# DCCGen_ATMEGA_V5.net
KiCad netlist of a schematic drawn in EAGLE
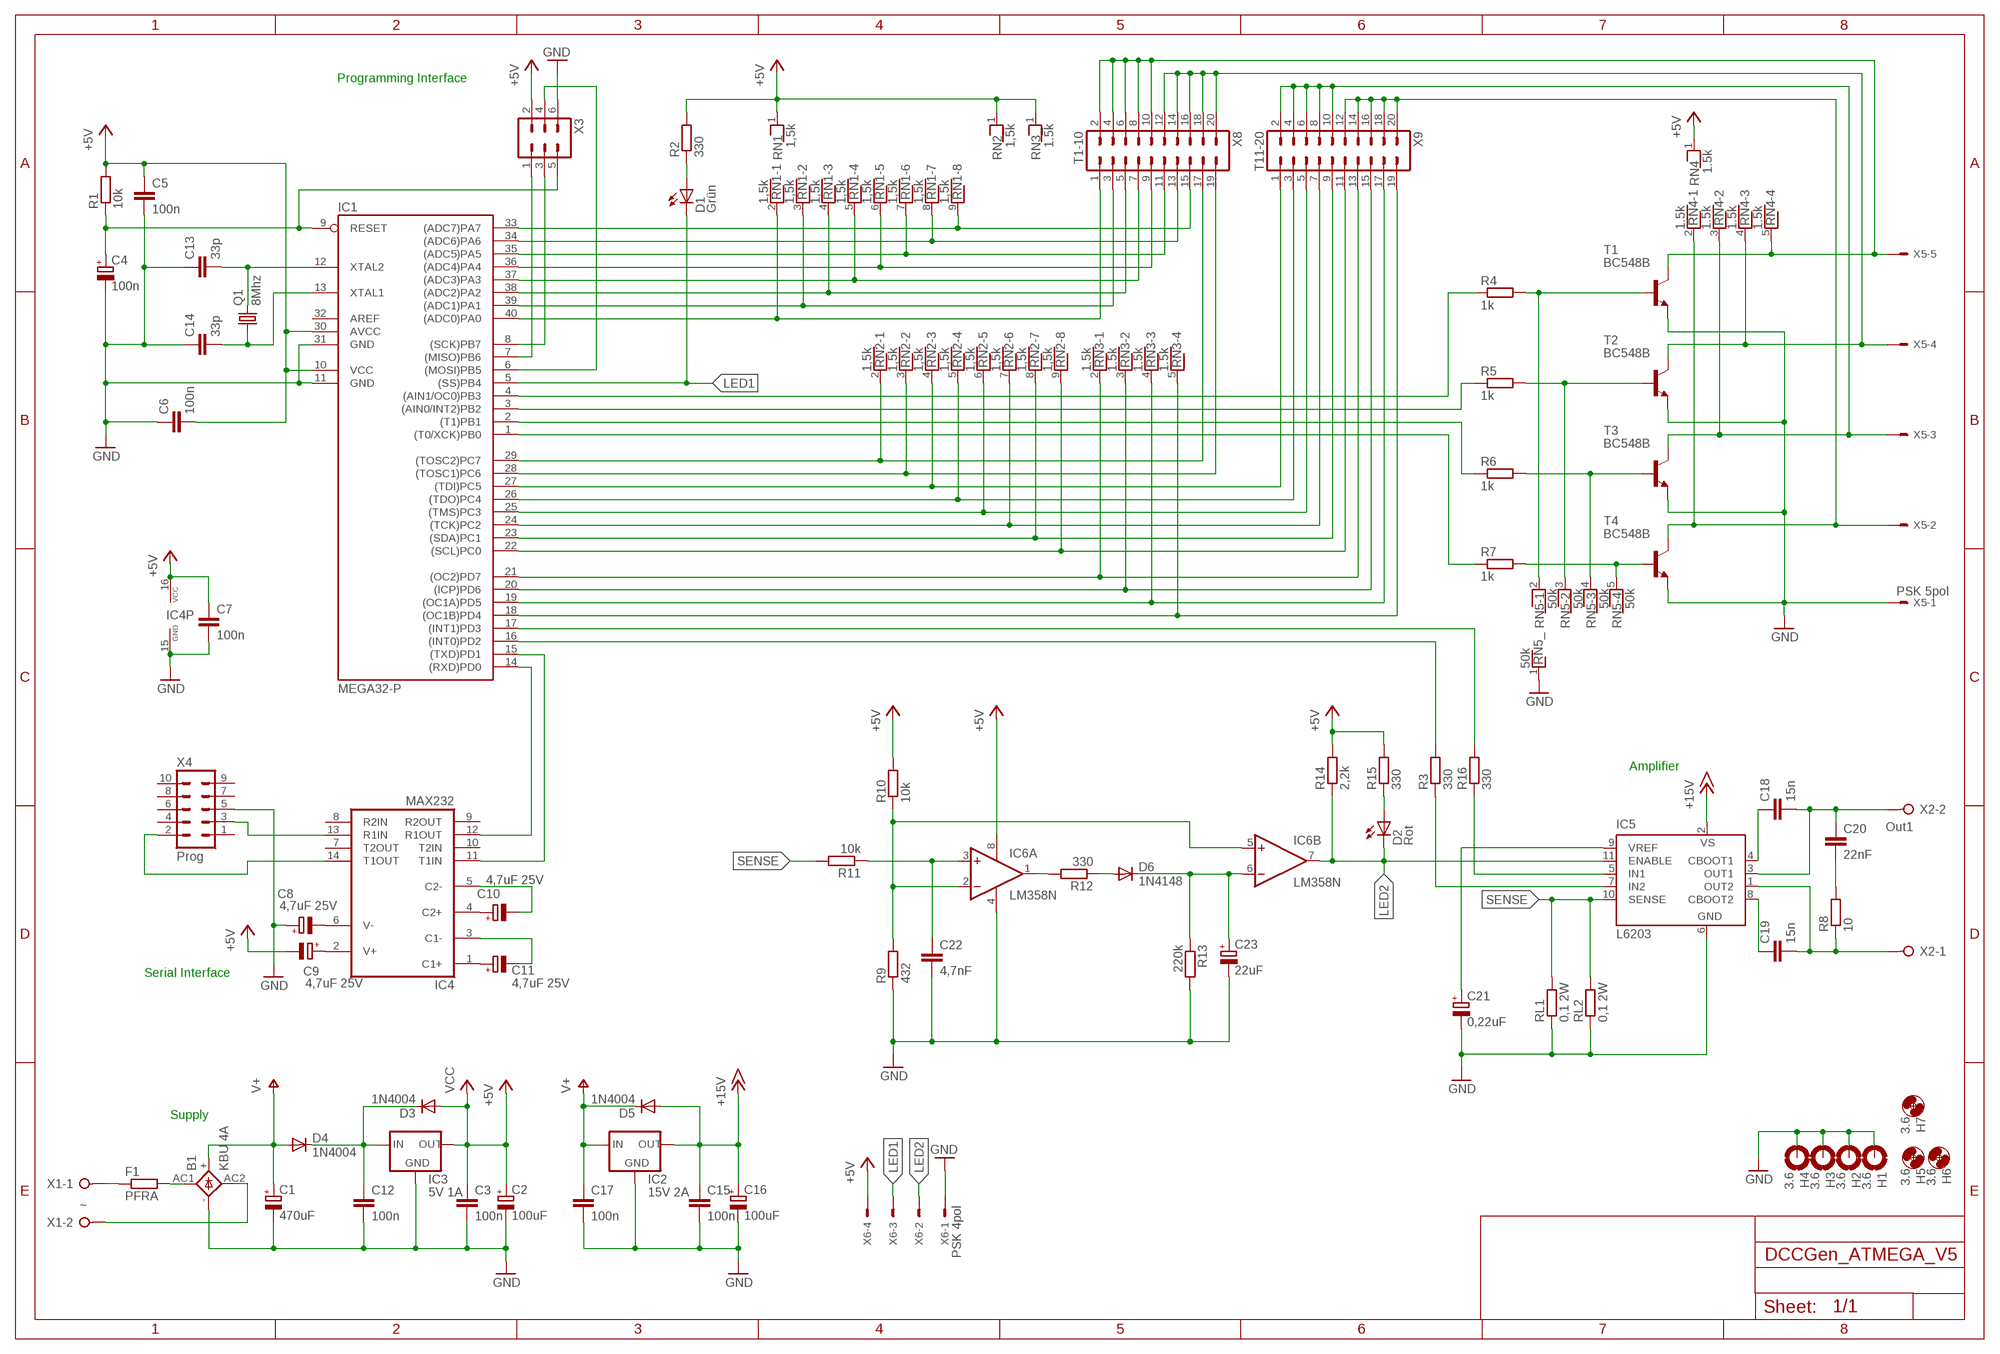
[diagram p0: schematic, sheet 1]

(export (version "E")
  (design (tool "Eeschema 10.0.6"))
  (components
    (comp (ref "B1")
      (value "KBU 4A")
      (footprint "eagle-import:KBU")
      (libsource (lib "eagle-import") (part "KBU"))
    )
    (comp (ref "C1")
      (value "470uF")
      (footprint "eagle-import:E5-13")
      (libsource (lib "eagle-import") (part "CPOL-EUE5-13"))
    )
    (comp (ref "C2")
      (value "100uF")
      (footprint "eagle-import:E2,5-7")
      (libsource (lib "eagle-import") (part "CPOL-EUE2.5-7"))
    )
    (comp (ref "C3")
      (value "100n")
      (footprint "eagle-import:C025-025X050")
      (libsource (lib "eagle-import") (part "C-EU025-025X050"))
    )
    (comp (ref "C4")
      (value "100n")
      (footprint "eagle-import:E2,5-5")
      (libsource (lib "eagle-import") (part "CPOL-EUE2.5-5"))
    )
    (comp (ref "C5")
      (value "100n")
      (footprint "eagle-import:C025-025X050")
      (libsource (lib "eagle-import") (part "C-EU025-025X050"))
    )
    (comp (ref "C6")
      (value "100n")
      (footprint "eagle-import:C025-025X050")
      (libsource (lib "eagle-import") (part "C-EU025-025X050"))
    )
    (comp (ref "C7")
      (value "100n")
      (footprint "eagle-import:C025-025X050")
      (libsource (lib "eagle-import") (part "C-EU025-025X050"))
    )
    (comp (ref "C8")
      (value "4,7uF 25V")
      (footprint "eagle-import:E2,5-6E")
      (libsource (lib "eagle-import") (part "CPOL-EUE2,5-6E"))
    )
    (comp (ref "C9")
      (value "4,7uF 25V")
      (footprint "eagle-import:E2,5-6E")
      (libsource (lib "eagle-import") (part "CPOL-EUE2,5-6E"))
    )
    (comp (ref "C10")
      (value "4,7uF 25V")
      (footprint "eagle-import:E2,5-6E")
      (libsource (lib "eagle-import") (part "CPOL-EUE2,5-6E"))
    )
    (comp (ref "C11")
      (value "4,7uF 25V")
      (footprint "eagle-import:E2,5-6E")
      (libsource (lib "eagle-import") (part "CPOL-EUE2,5-6E"))
    )
    (comp (ref "C12")
      (value "100n")
      (footprint "eagle-import:C025-025X050")
      (libsource (lib "eagle-import") (part "C-EU025-025X050"))
    )
    (comp (ref "C13")
      (value "33p")
      (footprint "eagle-import:C025-025X050")
      (libsource (lib "eagle-import") (part "C-EU025-025X050"))
    )
    (comp (ref "C14")
      (value "33p")
      (footprint "eagle-import:C025-025X050")
      (libsource (lib "eagle-import") (part "C-EU025-025X050"))
    )
    (comp (ref "C15")
      (value "100n")
      (footprint "eagle-import:C025-025X050")
      (libsource (lib "eagle-import") (part "C-EU025-025X050"))
    )
    (comp (ref "C16")
      (value "100uF")
      (footprint "eagle-import:E2,5-7")
      (libsource (lib "eagle-import") (part "CPOL-EUE2.5-7"))
    )
    (comp (ref "C17")
      (value "100n")
      (footprint "eagle-import:C025-025X050")
      (libsource (lib "eagle-import") (part "C-EU025-025X050"))
    )
    (comp (ref "C18")
      (value "15n")
      (footprint "eagle-import:C025-025X050")
      (libsource (lib "eagle-import") (part "C-EU025-025X050"))
    )
    (comp (ref "C19")
      (value "15n")
      (footprint "eagle-import:C025-025X050")
      (libsource (lib "eagle-import") (part "C-EU025-025X050"))
    )
    (comp (ref "C20")
      (value "22nF")
      (footprint "eagle-import:C025-025X050")
      (libsource (lib "eagle-import") (part "C-EU025-025X050"))
    )
    (comp (ref "C21")
      (value "0,22uF")
      (footprint "eagle-import:E2-5")
      (libsource (lib "eagle-import") (part "CPOL-EUE2-5"))
    )
    (comp (ref "C22")
      (value "4,7nF")
      (footprint "eagle-import:C025-025X050")
      (libsource (lib "eagle-import") (part "C-EU025-025X050"))
    )
    (comp (ref "C23")
      (value "22uF")
      (footprint "eagle-import:E2-5")
      (libsource (lib "eagle-import") (part "CPOL-EUE2-5"))
    )
    (comp (ref "D1")
      (value "Grün")
      (footprint "eagle-import:LED3MM")
      (libsource (lib "eagle-import") (part "LED3MM"))
    )
    (comp (ref "D2")
      (value "Rot")
      (footprint "eagle-import:LED3MM")
      (libsource (lib "eagle-import") (part "LED3MM"))
    )
    (comp (ref "D3")
      (value "1N4004")
      (footprint "eagle-import:DO41-10")
      (libsource (lib "eagle-import") (part "1N4004"))
    )
    (comp (ref "D4")
      (value "1N4004")
      (footprint "eagle-import:DO41-10")
      (libsource (lib "eagle-import") (part "1N4004"))
    )
    (comp (ref "D5")
      (value "1N4004")
      (footprint "eagle-import:DO41-10")
      (libsource (lib "eagle-import") (part "1N4004"))
    )
    (comp (ref "D6")
      (value "1N4148")
      (footprint "eagle-import:DO35-10")
      (libsource (lib "eagle-import") (part "1N4148DO35-10"))
    )
    (comp (ref "F1")
      (value "PFRA")
      (footprint "eagle-import:0204_5")
      (libsource (lib "eagle-import") (part "R-EU_0204/5"))
    )
    (comp (ref "H1")
      (value "3.6")
      (footprint "eagle-import:3,6-PAD")
      (libsource (lib "eagle-import") (part "MOUNT-PAD-ROUND3.6"))
    )
    (comp (ref "H2")
      (value "3.6")
      (footprint "eagle-import:3,6-PAD")
      (libsource (lib "eagle-import") (part "MOUNT-PAD-ROUND3.6"))
    )
    (comp (ref "H3")
      (value "3.6")
      (footprint "eagle-import:3,6-PAD")
      (libsource (lib "eagle-import") (part "MOUNT-PAD-ROUND3.6"))
    )
    (comp (ref "H4")
      (value "3.6")
      (footprint "eagle-import:3,6-PAD")
      (libsource (lib "eagle-import") (part "MOUNT-PAD-ROUND3.6"))
    )
    (comp (ref "H5")
      (value "3.6")
      (footprint "eagle-import:3,6")
      (libsource (lib "eagle-import") (part "MOUNT-HOLE3.6"))
    )
    (comp (ref "H6")
      (value "3.6")
      (footprint "eagle-import:3,6")
      (libsource (lib "eagle-import") (part "MOUNT-HOLE3.6"))
    )
    (comp (ref "H7")
      (value "3.6")
      (footprint "eagle-import:3,6")
      (libsource (lib "eagle-import") (part "MOUNT-HOLE3.6"))
    )
    (comp (ref "IC1")
      (value "MEGA32-P")
      (footprint "eagle-import:DIL40")
      (fields (field (name "MPN") "ATMEGA32-16PU"))
      (libsource (lib "eagle-import") (part "MEGA32-P"))
    )
    (comp (ref "IC2")
      (value "15V 2A")
      (footprint "eagle-import:78XXS")
      (libsource (lib "eagle-import") (part "78XXS"))
    )
    (comp (ref "IC3")
      (value "5V 1A")
      (footprint "eagle-import:78XXS")
      (libsource (lib "eagle-import") (part "78XXS"))
    )
    (comp (ref "IC4")
      (value "MAX232")
      (footprint "eagle-import:DIL16")
      (libsource (lib "eagle-import") (part "MAX232"))
    )
    (comp (ref "IC5")
      (value "L6203")
      (footprint "eagle-import:MULTIWATT-11")
      (libsource (lib "eagle-import") (part "L6203"))
    )
    (comp (ref "IC6")
      (value "LM358N")
      (footprint "eagle-import:DIL08")
      (libsource (lib "eagle-import") (part "LM358N"))
    )
    (comp (ref "Q1")
      (value "8Mhz")
      (footprint "eagle-import:HC49U-V")
      (libsource (lib "eagle-import") (part "CRYSTALHC49U-V"))
    )
    (comp (ref "R1")
      (value "10k")
      (footprint "eagle-import:0207_10")
      (libsource (lib "eagle-import") (part "R-EU_0207/10"))
    )
    (comp (ref "R2")
      (value "330")
      (footprint "eagle-import:0207_10")
      (libsource (lib "eagle-import") (part "R-EU_0207/10"))
    )
    (comp (ref "R3")
      (value "330")
      (footprint "eagle-import:0207_10")
      (libsource (lib "eagle-import") (part "R-EU_0207/10"))
    )
    (comp (ref "R4")
      (value "1k")
      (footprint "eagle-import:0207_10")
      (libsource (lib "eagle-import") (part "R-EU_0207/10"))
    )
    (comp (ref "R5")
      (value "1k")
      (footprint "eagle-import:0207_10")
      (libsource (lib "eagle-import") (part "R-EU_0207/10"))
    )
    (comp (ref "R6")
      (value "1k")
      (footprint "eagle-import:0207_10")
      (libsource (lib "eagle-import") (part "R-EU_0207/10"))
    )
    (comp (ref "R7")
      (value "1k")
      (footprint "eagle-import:0207_10")
      (libsource (lib "eagle-import") (part "R-EU_0207/10"))
    )
    (comp (ref "R8")
      (value "10")
      (footprint "eagle-import:0207_10")
      (libsource (lib "eagle-import") (part "R-EU_0207/10"))
    )
    (comp (ref "R9")
      (value "432")
      (footprint "eagle-import:0207_10")
      (libsource (lib "eagle-import") (part "R-EU_0207/10"))
    )
    (comp (ref "R10")
      (value "10k")
      (footprint "eagle-import:0207_10")
      (libsource (lib "eagle-import") (part "R-EU_0207/10"))
    )
    (comp (ref "R11")
      (value "10k")
      (footprint "eagle-import:0207_10")
      (libsource (lib "eagle-import") (part "R-EU_0207/10"))
    )
    (comp (ref "R12")
      (value "330")
      (footprint "eagle-import:0207_10")
      (libsource (lib "eagle-import") (part "R-EU_0207/10"))
    )
    (comp (ref "R13")
      (value "220k")
      (footprint "eagle-import:0207_10")
      (libsource (lib "eagle-import") (part "R-EU_0207/10"))
    )
    (comp (ref "R14")
      (value "2,2k")
      (footprint "eagle-import:0207_10")
      (libsource (lib "eagle-import") (part "R-EU_0207/10"))
    )
    (comp (ref "R15")
      (value "330")
      (footprint "eagle-import:0207_10")
      (libsource (lib "eagle-import") (part "R-EU_0207/10"))
    )
    (comp (ref "R16")
      (value "330")
      (footprint "eagle-import:0207_10")
      (libsource (lib "eagle-import") (part "R-EU_0207/10"))
    )
    (comp (ref "RL1")
      (value "0,1 2W")
      (footprint "eagle-import:0617_17")
      (libsource (lib "eagle-import") (part "R-EU_0617/17"))
    )
    (comp (ref "RL2")
      (value "0,1 2W")
      (footprint "eagle-import:0617_17")
      (libsource (lib "eagle-import") (part "R-EU_0617/17"))
    )
    (comp (ref "RN1")
      (value "1,5k")
      (footprint "eagle-import:RN-9")
      (libsource (lib "eagle-import") (part "RNX8"))
    )
    (comp (ref "RN2")
      (value "1,5k")
      (footprint "eagle-import:RN-9")
      (libsource (lib "eagle-import") (part "RNX8"))
    )
    (comp (ref "RN3")
      (value "1.5k")
      (footprint "eagle-import:RN-5")
      (fields (field (name "OC_FARNELL") "unknown") (field (name "OC_NEWARK") "unknown"))
      (libsource (lib "eagle-import") (part "RNX4"))
    )
    (comp (ref "RN4")
      (value "1.5k")
      (footprint "eagle-import:RN-5")
      (libsource (lib "eagle-import") (part "RNX4"))
    )
    (comp (ref "RN5")
      (value "50k")
      (footprint "eagle-import:RN-5")
      (libsource (lib "eagle-import") (part "RNX4"))
    )
    (comp (ref "T1")
      (value "BC548B")
      (footprint "eagle-import:TO92-EBC")
      (libsource (lib "eagle-import") (part "BC548B"))
    )
    (comp (ref "T2")
      (value "BC548B")
      (footprint "eagle-import:TO92-EBC")
      (libsource (lib "eagle-import") (part "BC548B"))
    )
    (comp (ref "T3")
      (value "BC548B")
      (footprint "eagle-import:TO92-EBC")
      (libsource (lib "eagle-import") (part "BC548B"))
    )
    (comp (ref "T4")
      (value "BC548B")
      (footprint "eagle-import:TO92-EBC")
      (libsource (lib "eagle-import") (part "BC548B"))
    )
    (comp (ref "X1")
      (value "~")
      (footprint "eagle-import:W237-132")
      (libsource (lib "eagle-import") (part "W237-02P"))
    )
    (comp (ref "X2")
      (value "Out1")
      (footprint "eagle-import:W237-132")
      (libsource (lib "eagle-import") (part "W237-02P"))
    )
    (comp (ref "X3")
      (value "ML6")
      (footprint "eagle-import:ML6")
      (libsource (lib "eagle-import") (part "ML6"))
    )
    (comp (ref "X4")
      (value "Prog")
      (footprint "eagle-import:ML10")
      (libsource (lib "eagle-import") (part "ML10"))
    )
    (comp (ref "X5")
      (value "PSK 5pol")
      (footprint "eagle-import:6410-05")
      (libsource (lib "eagle-import") (part "22-?-0527-2051"))
    )
    (comp (ref "X6")
      (value "PSK 4pol")
      (footprint "eagle-import:6410-04")
      (libsource (lib "eagle-import") (part "22-?-0427-2041"))
    )
    (comp (ref "X8")
      (value "T1-10")
      (footprint "eagle-import:ML20")
      (libsource (lib "eagle-import") (part "ML20"))
    )
    (comp (ref "X9")
      (value "T11-20")
      (footprint "eagle-import:ML20")
      (libsource (lib "eagle-import") (part "ML20"))
    )
  )
  (nets
    (net (code "1") (name "+5V") (class "Default")
      (node (ref "C2") (pin "+") (pinfunction "+_+") (pintype "passive"))
      (node (ref "C3") (pin "1") (pinfunction "1_1") (pintype "passive"))
      (node (ref "C5") (pin "1") (pinfunction "1_1") (pintype "passive"))
      (node (ref "C6") (pin "2") (pinfunction "2_2") (pintype "passive"))
      (node (ref "C7") (pin "1") (pinfunction "1_1") (pintype "passive"))
      (node (ref "C9") (pin "-") (pinfunction "-_-") (pintype "passive"))
      (node (ref "D3") (pin "A") (pinfunction "A_A") (pintype "passive"))
      (node (ref "IC1") (pin "10") (pinfunction "VCC_10") (pintype "power_in"))
      (node (ref "IC1") (pin "30") (pinfunction "AVCC_30") (pintype "power_in"))
      (node (ref "IC3") (pin "OUT") (pinfunction "OUT_OUT") (pintype "passive"))
      (node (ref "IC4") (pin "16") (pinfunction "VCC_16") (pintype "power_in"))
      (node (ref "IC6") (pin "8") (pinfunction "V+_8") (pintype "power_in"))
      (node (ref "R1") (pin "2") (pinfunction "2_2") (pintype "passive"))
      (node (ref "R10") (pin "2") (pinfunction "2_2") (pintype "passive"))
      (node (ref "R14") (pin "2") (pinfunction "2_2") (pintype "passive"))
      (node (ref "R15") (pin "2") (pinfunction "2_2") (pintype "passive"))
      (node (ref "R2") (pin "2") (pinfunction "2_2") (pintype "passive"))
      (node (ref "RN1") (pin "1") (pinfunction "1_1") (pintype "passive"))
      (node (ref "RN2") (pin "1") (pinfunction "1_1") (pintype "passive"))
      (node (ref "RN3") (pin "1") (pinfunction "1_1") (pintype "passive"))
      (node (ref "RN4") (pin "1") (pinfunction "1_1") (pintype "passive"))
      (node (ref "X3") (pin "2") (pinfunction "2_2") (pintype "passive"))
      (node (ref "X6") (pin "4") (pinfunction "S_4") (pintype "passive"))
    )
    (net (code "2") (name "+15V") (class "Default")
      (node (ref "C15") (pin "1") (pinfunction "1_1") (pintype "passive"))
      (node (ref "C16") (pin "+") (pinfunction "+_+") (pintype "passive"))
      (node (ref "D5") (pin "A") (pinfunction "A_A") (pintype "passive"))
      (node (ref "IC2") (pin "OUT") (pinfunction "OUT_OUT") (pintype "passive"))
      (node (ref "IC5") (pin "2") (pinfunction "VS_2") (pintype "power_in"))
    )
    (net (code "3") (name "GND") (class "Default")
      (node (ref "B1") (pin "-") (pinfunction "-_-") (pintype "passive"))
      (node (ref "C1") (pin "-") (pinfunction "-_-") (pintype "passive"))
      (node (ref "C12") (pin "2") (pinfunction "2_2") (pintype "passive"))
      (node (ref "C13") (pin "1") (pinfunction "1_1") (pintype "passive"))
      (node (ref "C14") (pin "1") (pinfunction "1_1") (pintype "passive"))
      (node (ref "C15") (pin "2") (pinfunction "2_2") (pintype "passive"))
      (node (ref "C16") (pin "-") (pinfunction "-_-") (pintype "passive"))
      (node (ref "C17") (pin "2") (pinfunction "2_2") (pintype "passive"))
      (node (ref "C2") (pin "-") (pinfunction "-_-") (pintype "passive"))
      (node (ref "C21") (pin "-") (pinfunction "-_-") (pintype "passive"))
      (node (ref "C22") (pin "2") (pinfunction "2_2") (pintype "passive"))
      (node (ref "C23") (pin "-") (pinfunction "-_-") (pintype "passive"))
      (node (ref "C3") (pin "2") (pinfunction "2_2") (pintype "passive"))
      (node (ref "C4") (pin "-") (pinfunction "-_-") (pintype "passive"))
      (node (ref "C5") (pin "2") (pinfunction "2_2") (pintype "passive"))
      (node (ref "C6") (pin "1") (pinfunction "1_1") (pintype "passive"))
      (node (ref "C7") (pin "2") (pinfunction "2_2") (pintype "passive"))
      (node (ref "C8") (pin "+") (pinfunction "+_+") (pintype "passive"))
      (node (ref "H1") (pin "B3,6") (pinfunction "MOUNT_B3,6") (pintype "passive"))
      (node (ref "H2") (pin "B3,6") (pinfunction "MOUNT_B3,6") (pintype "passive"))
      (node (ref "H3") (pin "B3,6") (pinfunction "MOUNT_B3,6") (pintype "passive"))
      (node (ref "H4") (pin "B3,6") (pinfunction "MOUNT_B3,6") (pintype "passive"))
      (node (ref "IC1") (pin "11") (pinfunction "GND_11") (pintype "power_in"))
      (node (ref "IC1") (pin "31") (pinfunction "GND_31") (pintype "power_in"))
      (node (ref "IC2") (pin "GND") (pinfunction "GND_GND") (pintype "input"))
      (node (ref "IC3") (pin "GND") (pinfunction "GND_GND") (pintype "input"))
      (node (ref "IC4") (pin "15") (pinfunction "GND_15") (pintype "power_in"))
      (node (ref "IC5") (pin "6") (pinfunction "GND_6") (pintype "power_in"))
      (node (ref "IC6") (pin "4") (pinfunction "V-_4") (pintype "power_in"))
      (node (ref "R13") (pin "2") (pinfunction "2_2") (pintype "passive"))
      (node (ref "R9") (pin "1") (pinfunction "1_1") (pintype "passive"))
      (node (ref "RL1") (pin "1") (pinfunction "1_1") (pintype "passive"))
      (node (ref "RL2") (pin "1") (pinfunction "1_1") (pintype "passive"))
      (node (ref "RN5") (pin "1") (pinfunction "1_1") (pintype "passive"))
      (node (ref "T1") (pin "E") (pinfunction "E_E") (pintype "passive"))
      (node (ref "T2") (pin "E") (pinfunction "E_E") (pintype "passive"))
      (node (ref "T3") (pin "E") (pinfunction "E_E") (pintype "passive"))
      (node (ref "T4") (pin "E") (pinfunction "E_E") (pintype "passive"))
      (node (ref "X3") (pin "6") (pinfunction "6_6") (pintype "passive"))
      (node (ref "X4") (pin "5") (pinfunction "5_5") (pintype "passive"))
      (node (ref "X5") (pin "1") (pinfunction "S_1") (pintype "passive"))
      (node (ref "X6") (pin "1") (pinfunction "S_1") (pintype "passive"))
    )
    (net (code "4") (name "LED1") (class "Default")
      (node (ref "D1") (pin "K") (pinfunction "C_K") (pintype "passive"))
      (node (ref "IC1") (pin "5") (pinfunction "(SS)PB4_5") (pintype "bidirectional"))
      (node (ref "X6") (pin "3") (pinfunction "S_3") (pintype "passive"))
    )
    (net (code "5") (name "LED2") (class "Default")
      (node (ref "D2") (pin "K") (pinfunction "C_K") (pintype "passive"))
      (node (ref "IC5") (pin "11") (pinfunction "ENABLE_11") (pintype "input"))
      (node (ref "IC6") (pin "7") (pinfunction "OUT_7") (pintype "output"))
      (node (ref "R14") (pin "1") (pinfunction "1_1") (pintype "passive"))
      (node (ref "X6") (pin "2") (pinfunction "S_2") (pintype "passive"))
    )
    (net (code "6") (name "Net-(B1-PadAC1)") (class "Default")
      (node (ref "B1") (pin "AC1") (pinfunction "AC1_AC1") (pintype "passive"))
      (node (ref "F1") (pin "2") (pinfunction "2_2") (pintype "passive"))
    )
    (net (code "7") (name "Net-(C12-Pad1)") (class "Default")
      (node (ref "C12") (pin "1") (pinfunction "1_1") (pintype "passive"))
      (node (ref "D3") (pin "C") (pinfunction "C_C") (pintype "passive"))
      (node (ref "D4") (pin "C") (pinfunction "C_C") (pintype "passive"))
      (node (ref "IC3") (pin "IN") (pinfunction "IN_IN") (pintype "input"))
    )
    (net (code "8") (name "Net-(C20-Pad2)") (class "Default")
      (node (ref "C20") (pin "2") (pinfunction "2_2") (pintype "passive"))
      (node (ref "R8") (pin "2") (pinfunction "2_2") (pintype "passive"))
    )
    (net (code "9") (name "Net-(D1-PadA)") (class "Default")
      (node (ref "D1") (pin "A") (pinfunction "A_A") (pintype "passive"))
      (node (ref "R2") (pin "1") (pinfunction "1_1") (pintype "passive"))
    )
    (net (code "10") (name "Net-(D2-PadA)") (class "Default")
      (node (ref "D2") (pin "A") (pinfunction "A_A") (pintype "passive"))
      (node (ref "R15") (pin "1") (pinfunction "1_1") (pintype "passive"))
    )
    (net (code "11") (name "Net-(D6-PadA)") (class "Default")
      (node (ref "D6") (pin "A") (pinfunction "A_A") (pintype "passive"))
      (node (ref "R12") (pin "1") (pinfunction "1_1") (pintype "passive"))
    )
    (net (code "12") (name "Net-(IC1-(ADC0)PA0)") (class "Default")
      (node (ref "IC1") (pin "40") (pinfunction "(ADC0)PA0_40") (pintype "bidirectional"))
      (node (ref "RN1") (pin "2") (pinfunction "1_2") (pintype "passive"))
      (node (ref "X8") (pin "1") (pinfunction "1_1") (pintype "passive"))
    )
    (net (code "13") (name "Net-(IC1-(ADC1)PA1)") (class "Default")
      (node (ref "IC1") (pin "39") (pinfunction "(ADC1)PA1_39") (pintype "bidirectional"))
      (node (ref "RN1") (pin "3") (pinfunction "1_3") (pintype "passive"))
      (node (ref "X8") (pin "3") (pinfunction "3_3") (pintype "passive"))
    )
    (net (code "14") (name "Net-(IC1-(ADC2)PA2)") (class "Default")
      (node (ref "IC1") (pin "38") (pinfunction "(ADC2)PA2_38") (pintype "bidirectional"))
      (node (ref "RN1") (pin "4") (pinfunction "1_4") (pintype "passive"))
      (node (ref "X8") (pin "5") (pinfunction "5_5") (pintype "passive"))
    )
    (net (code "15") (name "Net-(IC1-(ADC3)PA3)") (class "Default")
      (node (ref "IC1") (pin "37") (pinfunction "(ADC3)PA3_37") (pintype "bidirectional"))
      (node (ref "RN1") (pin "5") (pinfunction "1_5") (pintype "passive"))
      (node (ref "X8") (pin "7") (pinfunction "7_7") (pintype "passive"))
    )
    (net (code "16") (name "Net-(IC1-(ADC4)PA4)") (class "Default")
      (node (ref "IC1") (pin "36") (pinfunction "(ADC4)PA4_36") (pintype "bidirectional"))
      (node (ref "RN1") (pin "6") (pinfunction "1_6") (pintype "passive"))
      (node (ref "X8") (pin "9") (pinfunction "9_9") (pintype "passive"))
    )
    (net (code "17") (name "Net-(IC1-(ADC5)PA5)") (class "Default")
      (node (ref "IC1") (pin "35") (pinfunction "(ADC5)PA5_35") (pintype "bidirectional"))
      (node (ref "RN1") (pin "7") (pinfunction "1_7") (pintype "passive"))
      (node (ref "X8") (pin "11") (pinfunction "11_11") (pintype "passive"))
    )
    (net (code "18") (name "Net-(IC1-(ADC6)PA6)") (class "Default")
      (node (ref "IC1") (pin "34") (pinfunction "(ADC6)PA6_34") (pintype "bidirectional"))
      (node (ref "RN1") (pin "8") (pinfunction "1_8") (pintype "passive"))
      (node (ref "X8") (pin "13") (pinfunction "13_13") (pintype "passive"))
    )
    (net (code "19") (name "Net-(IC1-(ADC7)PA7)") (class "Default")
      (node (ref "IC1") (pin "33") (pinfunction "(ADC7)PA7_33") (pintype "bidirectional"))
      (node (ref "RN1") (pin "9") (pinfunction "1_9") (pintype "passive"))
      (node (ref "X8") (pin "15") (pinfunction "15_15") (pintype "passive"))
    )
    (net (code "20") (name "Net-(IC1-(AIN0{slash}INT2)PB2)") (class "Default")
      (node (ref "IC1") (pin "3") (pinfunction "(AIN0/INT2)PB2_3") (pintype "bidirectional"))
      (node (ref "R5") (pin "1") (pinfunction "1_1") (pintype "passive"))
    )
    (net (code "21") (name "Net-(IC1-(AIN1{slash}OC0)PB3)") (class "Default")
      (node (ref "IC1") (pin "4") (pinfunction "(AIN1/OC0)PB3_4") (pintype "bidirectional"))
      (node (ref "R4") (pin "1") (pinfunction "1_1") (pintype "passive"))
    )
    (net (code "22") (name "Net-(IC1-(ICP)PD6)") (class "Default")
      (node (ref "IC1") (pin "20") (pinfunction "(ICP)PD6_20") (pintype "bidirectional"))
      (node (ref "RN3") (pin "3") (pinfunction "1_3") (pintype "passive"))
      (node (ref "X9") (pin "15") (pinfunction "15_15") (pintype "passive"))
    )
    (net (code "23") (name "Net-(IC1-(INT0)PD2)") (class "Default")
      (node (ref "IC1") (pin "16") (pinfunction "(INT0)PD2_16") (pintype "bidirectional"))
      (node (ref "R3") (pin "2") (pinfunction "2_2") (pintype "passive"))
    )
    (net (code "24") (name "Net-(IC1-(INT1)PD3)") (class "Default")
      (node (ref "IC1") (pin "17") (pinfunction "(INT1)PD3_17") (pintype "bidirectional"))
      (node (ref "R16") (pin "2") (pinfunction "2_2") (pintype "passive"))
    )
    (net (code "25") (name "Net-(IC1-(MISO)PB6)") (class "Default")
      (node (ref "IC1") (pin "7") (pinfunction "(MISO)PB6_7") (pintype "bidirectional"))
      (node (ref "X3") (pin "1") (pinfunction "1_1") (pintype "passive"))
    )
    (net (code "26") (name "Net-(IC1-(MOSI)PB5)") (class "Default")
      (node (ref "IC1") (pin "6") (pinfunction "(MOSI)PB5_6") (pintype "bidirectional"))
      (node (ref "X3") (pin "4") (pinfunction "4_4") (pintype "passive"))
    )
    (net (code "27") (name "Net-(IC1-(OC1A)PD5)") (class "Default")
      (node (ref "IC1") (pin "19") (pinfunction "(OC1A)PD5_19") (pintype "bidirectional"))
      (node (ref "RN3") (pin "4") (pinfunction "1_4") (pintype "passive"))
      (node (ref "X9") (pin "17") (pinfunction "17_17") (pintype "passive"))
    )
    (net (code "28") (name "Net-(IC1-(OC1B)PD4)") (class "Default")
      (node (ref "IC1") (pin "18") (pinfunction "(OC1B)PD4_18") (pintype "bidirectional"))
      (node (ref "RN3") (pin "5") (pinfunction "1_5") (pintype "passive"))
      (node (ref "X9") (pin "19") (pinfunction "19_19") (pintype "passive"))
    )
    (net (code "29") (name "Net-(IC1-(OC2)PD7)") (class "Default")
      (node (ref "IC1") (pin "21") (pinfunction "(OC2)PD7_21") (pintype "bidirectional"))
      (node (ref "RN3") (pin "2") (pinfunction "1_2") (pintype "passive"))
      (node (ref "X9") (pin "13") (pinfunction "13_13") (pintype "passive"))
    )
    (net (code "30") (name "Net-(IC1-(RXD)PD0)") (class "Default")
      (node (ref "IC1") (pin "14") (pinfunction "(RXD)PD0_14") (pintype "bidirectional"))
      (node (ref "IC4") (pin "12") (pinfunction "R1OUT_12") (pintype "output"))
    )
    (net (code "31") (name "Net-(IC1-(SCK)PB7)") (class "Default")
      (node (ref "IC1") (pin "8") (pinfunction "(SCK)PB7_8") (pintype "bidirectional"))
      (node (ref "X3") (pin "3") (pinfunction "3_3") (pintype "passive"))
    )
    (net (code "32") (name "Net-(IC1-(SCL)PC0)") (class "Default")
      (node (ref "IC1") (pin "22") (pinfunction "(SCL)PC0_22") (pintype "bidirectional"))
      (node (ref "RN2") (pin "9") (pinfunction "1_9") (pintype "passive"))
      (node (ref "X9") (pin "11") (pinfunction "11_11") (pintype "passive"))
    )
    (net (code "33") (name "Net-(IC1-(SDA)PC1)") (class "Default")
      (node (ref "IC1") (pin "23") (pinfunction "(SDA)PC1_23") (pintype "bidirectional"))
      (node (ref "RN2") (pin "8") (pinfunction "1_8") (pintype "passive"))
      (node (ref "X9") (pin "9") (pinfunction "9_9") (pintype "passive"))
    )
    (net (code "34") (name "Net-(IC1-(T0{slash}XCK)PB0)") (class "Default")
      (node (ref "IC1") (pin "1") (pinfunction "(T0/XCK)PB0_1") (pintype "bidirectional"))
      (node (ref "R7") (pin "1") (pinfunction "1_1") (pintype "passive"))
    )
    (net (code "35") (name "Net-(IC1-(T1)PB1)") (class "Default")
      (node (ref "IC1") (pin "2") (pinfunction "(T1)PB1_2") (pintype "bidirectional"))
      (node (ref "R6") (pin "1") (pinfunction "1_1") (pintype "passive"))
    )
    (net (code "36") (name "Net-(IC1-(TCK)PC2)") (class "Default")
      (node (ref "IC1") (pin "24") (pinfunction "(TCK)PC2_24") (pintype "bidirectional"))
      (node (ref "RN2") (pin "7") (pinfunction "1_7") (pintype "passive"))
      (node (ref "X9") (pin "7") (pinfunction "7_7") (pintype "passive"))
    )
    (net (code "37") (name "Net-(IC1-(TDI)PC5)") (class "Default")
      (node (ref "IC1") (pin "27") (pinfunction "(TDI)PC5_27") (pintype "bidirectional"))
      (node (ref "RN2") (pin "4") (pinfunction "1_4") (pintype "passive"))
      (node (ref "X9") (pin "1") (pinfunction "1_1") (pintype "passive"))
    )
    (net (code "38") (name "Net-(IC1-(TDO)PC4)") (class "Default")
      (node (ref "IC1") (pin "26") (pinfunction "(TDO)PC4_26") (pintype "bidirectional"))
      (node (ref "RN2") (pin "5") (pinfunction "1_5") (pintype "passive"))
      (node (ref "X9") (pin "3") (pinfunction "3_3") (pintype "passive"))
    )
    (net (code "39") (name "Net-(IC1-(TMS)PC3)") (class "Default")
      (node (ref "IC1") (pin "25") (pinfunction "(TMS)PC3_25") (pintype "bidirectional"))
      (node (ref "RN2") (pin "6") (pinfunction "1_6") (pintype "passive"))
      (node (ref "X9") (pin "5") (pinfunction "5_5") (pintype "passive"))
    )
    (net (code "40") (name "Net-(IC1-(TOSC1)PC6)") (class "Default")
      (node (ref "IC1") (pin "28") (pinfunction "(TOSC1)PC6_28") (pintype "bidirectional"))
      (node (ref "RN2") (pin "3") (pinfunction "1_3") (pintype "passive"))
      (node (ref "X8") (pin "19") (pinfunction "19_19") (pintype "passive"))
    )
    (net (code "41") (name "Net-(IC1-(TOSC2)PC7)") (class "Default")
      (node (ref "IC1") (pin "29") (pinfunction "(TOSC2)PC7_29") (pintype "bidirectional"))
      (node (ref "RN2") (pin "2") (pinfunction "1_2") (pintype "passive"))
      (node (ref "X8") (pin "17") (pinfunction "17_17") (pintype "passive"))
    )
    (net (code "42") (name "Net-(IC1-(TXD)PD1)") (class "Default")
      (node (ref "IC1") (pin "15") (pinfunction "(TXD)PD1_15") (pintype "bidirectional"))
      (node (ref "IC4") (pin "11") (pinfunction "T1IN_11") (pintype "input"))
    )
    (net (code "43") (name "Net-(IC1-RESET)") (class "Default")
      (node (ref "C4") (pin "+") (pinfunction "+_+") (pintype "passive"))
      (node (ref "IC1") (pin "9") (pinfunction "RESET_9") (pintype "input"))
      (node (ref "R1") (pin "1") (pinfunction "1_1") (pintype "passive"))
      (node (ref "X3") (pin "5") (pinfunction "5_5") (pintype "passive"))
    )
    (net (code "44") (name "Net-(IC1-XTAL1)") (class "Default")
      (node (ref "C14") (pin "2") (pinfunction "2_2") (pintype "passive"))
      (node (ref "IC1") (pin "13") (pinfunction "XTAL1_13") (pintype "bidirectional"))
      (node (ref "Q1") (pin "1") (pinfunction "1_1") (pintype "passive"))
    )
    (net (code "45") (name "Net-(IC1-XTAL2)") (class "Default")
      (node (ref "C13") (pin "2") (pinfunction "2_2") (pintype "passive"))
      (node (ref "IC1") (pin "12") (pinfunction "XTAL2_12") (pintype "bidirectional"))
      (node (ref "Q1") (pin "2") (pinfunction "2_2") (pintype "passive"))
    )
    (net (code "46") (name "Net-(IC4A-C1+)") (class "Default")
      (node (ref "C11") (pin "+") (pinfunction "+_+") (pintype "passive"))
      (node (ref "IC4") (pin "1") (pinfunction "C1+_1") (pintype "bidirectional"))
    )
    (net (code "47") (name "Net-(IC4A-C1-)") (class "Default")
      (node (ref "C11") (pin "-") (pinfunction "-_-") (pintype "passive"))
      (node (ref "IC4") (pin "3") (pinfunction "C1-_3") (pintype "bidirectional"))
    )
    (net (code "48") (name "Net-(IC4A-C2+)") (class "Default")
      (node (ref "C10") (pin "+") (pinfunction "+_+") (pintype "passive"))
      (node (ref "IC4") (pin "4") (pinfunction "C2+_4") (pintype "bidirectional"))
    )
    (net (code "49") (name "Net-(IC4A-C2-)") (class "Default")
      (node (ref "C10") (pin "-") (pinfunction "-_-") (pintype "passive"))
      (node (ref "IC4") (pin "5") (pinfunction "C2-_5") (pintype "bidirectional"))
    )
    (net (code "50") (name "Net-(IC4A-R1IN)") (class "Default")
      (node (ref "IC4") (pin "13") (pinfunction "R1IN_13") (pintype "input"))
      (node (ref "X4") (pin "3") (pinfunction "3_3") (pintype "passive"))
    )
    (net (code "51") (name "Net-(IC4A-T1OUT)") (class "Default")
      (node (ref "IC4") (pin "14") (pinfunction "T1OUT_14") (pintype "output"))
      (node (ref "X4") (pin "2") (pinfunction "2_2") (pintype "passive"))
    )
    (net (code "52") (name "Net-(IC4A-V+)") (class "Default")
      (node (ref "C9") (pin "+") (pinfunction "+_+") (pintype "passive"))
      (node (ref "IC4") (pin "2") (pinfunction "V+_2") (pintype "bidirectional"))
    )
    (net (code "53") (name "Net-(IC4A-V-)") (class "Default")
      (node (ref "C8") (pin "-") (pinfunction "-_-") (pintype "passive"))
      (node (ref "IC4") (pin "6") (pinfunction "V-_6") (pintype "bidirectional"))
    )
    (net (code "54") (name "Net-(IC5-CBOOT1)") (class "Default")
      (node (ref "C18") (pin "1") (pinfunction "1_1") (pintype "passive"))
      (node (ref "IC5") (pin "4") (pinfunction "CBOOT1_4") (pintype "input"))
    )
    (net (code "55") (name "Net-(IC5-CBOOT2)") (class "Default")
      (node (ref "C19") (pin "1") (pinfunction "1_1") (pintype "passive"))
      (node (ref "IC5") (pin "8") (pinfunction "CBOOT2_8") (pintype "input"))
    )
    (net (code "56") (name "Net-(IC5-IN1)") (class "Default")
      (node (ref "IC5") (pin "5") (pinfunction "IN1_5") (pintype "input"))
      (node (ref "R16") (pin "1") (pinfunction "1_1") (pintype "passive"))
    )
    (net (code "57") (name "Net-(IC5-IN2)") (class "Default")
      (node (ref "IC5") (pin "7") (pinfunction "IN2_7") (pintype "input"))
      (node (ref "R3") (pin "1") (pinfunction "1_1") (pintype "passive"))
    )
    (net (code "58") (name "Net-(IC5-OUT1)") (class "Default")
      (node (ref "C18") (pin "2") (pinfunction "2_2") (pintype "passive"))
      (node (ref "C20") (pin "1") (pinfunction "1_1") (pintype "passive"))
      (node (ref "IC5") (pin "3") (pinfunction "OUT1_3") (pintype "output"))
      (node (ref "X2") (pin "2") (pinfunction "KL_2") (pintype "passive"))
    )
    (net (code "59") (name "Net-(IC5-OUT2)") (class "Default")
      (node (ref "C19") (pin "2") (pinfunction "2_2") (pintype "passive"))
      (node (ref "IC5") (pin "1") (pinfunction "OUT2_1") (pintype "output"))
      (node (ref "R8") (pin "1") (pinfunction "1_1") (pintype "passive"))
      (node (ref "X2") (pin "1") (pinfunction "KL_1") (pintype "passive"))
    )
    (net (code "60") (name "Net-(IC5-VREF)") (class "Default")
      (node (ref "C21") (pin "+") (pinfunction "+_+") (pintype "passive"))
      (node (ref "IC5") (pin "9") (pinfunction "VREF_9") (pintype "input"))
    )
    (net (code "61") (name "Net-(IC6A-+IN)") (class "Default")
      (node (ref "C22") (pin "1") (pinfunction "1_1") (pintype "passive"))
      (node (ref "IC6") (pin "3") (pinfunction "+IN_3") (pintype "input"))
      (node (ref "R11") (pin "1") (pinfunction "1_1") (pintype "passive"))
    )
    (net (code "62") (name "Net-(IC6A--IN)") (class "Default")
      (node (ref "IC6") (pin "2") (pinfunction "-IN_2") (pintype "input"))
      (node (ref "IC6") (pin "5") (pinfunction "+IN_5") (pintype "input"))
      (node (ref "R10") (pin "1") (pinfunction "1_1") (pintype "passive"))
      (node (ref "R9") (pin "2") (pinfunction "2_2") (pintype "passive"))
    )
    (net (code "63") (name "Net-(IC6A-OUT)") (class "Default")
      (node (ref "IC6") (pin "1") (pinfunction "OUT_1") (pintype "output"))
      (node (ref "R12") (pin "2") (pinfunction "2_2") (pintype "passive"))
    )
    (net (code "64") (name "Net-(IC6B--IN)") (class "Default")
      (node (ref "C23") (pin "+") (pinfunction "+_+") (pintype "passive"))
      (node (ref "D6") (pin "C") (pinfunction "C_C") (pintype "passive"))
      (node (ref "IC6") (pin "6") (pinfunction "-IN_6") (pintype "input"))
      (node (ref "R13") (pin "1") (pinfunction "1_1") (pintype "passive"))
    )
    (net (code "65") (name "Net-(RN4A-1)") (class "Default")
      (node (ref "RN4") (pin "2") (pinfunction "1_2") (pintype "passive"))
      (node (ref "T4") (pin "C") (pinfunction "C_C") (pintype "passive"))
      (node (ref "X5") (pin "2") (pinfunction "S_2") (pintype "passive"))
      (node (ref "X9") (pin "12") (pinfunction "12_12") (pintype "passive"))
      (node (ref "X9") (pin "14") (pinfunction "14_14") (pintype "passive"))
      (node (ref "X9") (pin "16") (pinfunction "16_16") (pintype "passive"))
      (node (ref "X9") (pin "18") (pinfunction "18_18") (pintype "passive"))
      (node (ref "X9") (pin "20") (pinfunction "20_20") (pintype "passive"))
    )
    (net (code "66") (name "Net-(RN4B-1)") (class "Default")
      (node (ref "RN4") (pin "3") (pinfunction "1_3") (pintype "passive"))
      (node (ref "T3") (pin "C") (pinfunction "C_C") (pintype "passive"))
      (node (ref "X5") (pin "3") (pinfunction "S_3") (pintype "passive"))
      (node (ref "X9") (pin "10") (pinfunction "10_10") (pintype "passive"))
      (node (ref "X9") (pin "2") (pinfunction "2_2") (pintype "passive"))
      (node (ref "X9") (pin "4") (pinfunction "4_4") (pintype "passive"))
      (node (ref "X9") (pin "6") (pinfunction "6_6") (pintype "passive"))
      (node (ref "X9") (pin "8") (pinfunction "8_8") (pintype "passive"))
    )
    (net (code "67") (name "Net-(RN4C-1)") (class "Default")
      (node (ref "RN4") (pin "4") (pinfunction "1_4") (pintype "passive"))
      (node (ref "T2") (pin "C") (pinfunction "C_C") (pintype "passive"))
      (node (ref "X5") (pin "4") (pinfunction "S_4") (pintype "passive"))
      (node (ref "X8") (pin "12") (pinfunction "12_12") (pintype "passive"))
      (node (ref "X8") (pin "14") (pinfunction "14_14") (pintype "passive"))
      (node (ref "X8") (pin "16") (pinfunction "16_16") (pintype "passive"))
      (node (ref "X8") (pin "18") (pinfunction "18_18") (pintype "passive"))
      (node (ref "X8") (pin "20") (pinfunction "20_20") (pintype "passive"))
    )
    (net (code "68") (name "Net-(RN4D-1)") (class "Default")
      (node (ref "RN4") (pin "5") (pinfunction "1_5") (pintype "passive"))
      (node (ref "T1") (pin "C") (pinfunction "C_C") (pintype "passive"))
      (node (ref "X5") (pin "5") (pinfunction "S_5") (pintype "passive"))
      (node (ref "X8") (pin "10") (pinfunction "10_10") (pintype "passive"))
      (node (ref "X8") (pin "2") (pinfunction "2_2") (pintype "passive"))
      (node (ref "X8") (pin "4") (pinfunction "4_4") (pintype "passive"))
      (node (ref "X8") (pin "6") (pinfunction "6_6") (pintype "passive"))
      (node (ref "X8") (pin "8") (pinfunction "8_8") (pintype "passive"))
    )
    (net (code "69") (name "Net-(RN5A-1)") (class "Default")
      (node (ref "R4") (pin "2") (pinfunction "2_2") (pintype "passive"))
      (node (ref "RN5") (pin "2") (pinfunction "1_2") (pintype "passive"))
      (node (ref "T1") (pin "B") (pinfunction "B_B") (pintype "passive"))
    )
    (net (code "70") (name "Net-(RN5B-1)") (class "Default")
      (node (ref "R5") (pin "2") (pinfunction "2_2") (pintype "passive"))
      (node (ref "RN5") (pin "3") (pinfunction "1_3") (pintype "passive"))
      (node (ref "T2") (pin "B") (pinfunction "B_B") (pintype "passive"))
    )
    (net (code "71") (name "Net-(RN5C-1)") (class "Default")
      (node (ref "R6") (pin "2") (pinfunction "2_2") (pintype "passive"))
      (node (ref "RN5") (pin "4") (pinfunction "1_4") (pintype "passive"))
      (node (ref "T3") (pin "B") (pinfunction "B_B") (pintype "passive"))
    )
    (net (code "72") (name "Net-(RN5D-1)") (class "Default")
      (node (ref "R7") (pin "2") (pinfunction "2_2") (pintype "passive"))
      (node (ref "RN5") (pin "5") (pinfunction "1_5") (pintype "passive"))
      (node (ref "T4") (pin "B") (pinfunction "B_B") (pintype "passive"))
    )
    (net (code "73") (name "Net-(X1A-KL)") (class "Default")
      (node (ref "F1") (pin "1") (pinfunction "1_1") (pintype "passive"))
      (node (ref "X1") (pin "1") (pinfunction "KL_1") (pintype "passive"))
    )
    (net (code "74") (name "Net-(X1B-KL)") (class "Default")
      (node (ref "B1") (pin "AC2") (pinfunction "AC2_AC2") (pintype "passive"))
      (node (ref "X1") (pin "2") (pinfunction "KL_2") (pintype "passive"))
    )
    (net (code "75") (name "SENSE") (class "Default")
      (node (ref "IC5") (pin "10") (pinfunction "SENSE_10") (pintype "input"))
      (node (ref "R11") (pin "2") (pinfunction "2_2") (pintype "passive"))
      (node (ref "RL1") (pin "2") (pinfunction "2_2") (pintype "passive"))
      (node (ref "RL2") (pin "2") (pinfunction "2_2") (pintype "passive"))
    )
    (net (code "76") (name "V+") (class "Default")
      (node (ref "B1") (pin "+") (pinfunction "+_+") (pintype "passive"))
      (node (ref "C1") (pin "+") (pinfunction "+_+") (pintype "passive"))
      (node (ref "C17") (pin "1") (pinfunction "1_1") (pintype "passive"))
      (node (ref "D4") (pin "A") (pinfunction "A_A") (pintype "passive"))
      (node (ref "D5") (pin "C") (pinfunction "C_C") (pintype "passive"))
      (node (ref "IC2") (pin "IN") (pinfunction "IN_IN") (pintype "input"))
    )
    (net (code "77") (name "unconnected-(IC1-AREF-Pad32)") (class "Default")
      (node (ref "IC1") (pin "32") (pinfunction "AREF_32") (pintype "passive"))
    )
    (net (code "78") (name "unconnected-(IC4A-R2IN-Pad8)") (class "Default")
      (node (ref "IC4") (pin "8") (pinfunction "R2IN_8") (pintype "input"))
    )
    (net (code "79") (name "unconnected-(IC4A-R2OUT-Pad9)") (class "Default")
      (node (ref "IC4") (pin "9") (pinfunction "R2OUT_9") (pintype "output"))
    )
    (net (code "80") (name "unconnected-(IC4A-T2IN-Pad10)") (class "Default")
      (node (ref "IC4") (pin "10") (pinfunction "T2IN_10") (pintype "input"))
    )
    (net (code "81") (name "unconnected-(IC4A-T2OUT-Pad7)") (class "Default")
      (node (ref "IC4") (pin "7") (pinfunction "T2OUT_7") (pintype "output"))
    )
    (net (code "82") (name "unconnected-(X4-Pad1)") (class "Default")
      (node (ref "X4") (pin "1") (pinfunction "1_1") (pintype "passive"))
    )
    (net (code "83") (name "unconnected-(X4-Pad4)") (class "Default")
      (node (ref "X4") (pin "4") (pinfunction "4_4") (pintype "passive"))
    )
    (net (code "84") (name "unconnected-(X4-Pad6)") (class "Default")
      (node (ref "X4") (pin "6") (pinfunction "6_6") (pintype "passive"))
    )
    (net (code "85") (name "unconnected-(X4-Pad7)") (class "Default")
      (node (ref "X4") (pin "7") (pinfunction "7_7") (pintype "passive"))
    )
    (net (code "86") (name "unconnected-(X4-Pad8)") (class "Default")
      (node (ref "X4") (pin "8") (pinfunction "8_8") (pintype "passive"))
    )
    (net (code "87") (name "unconnected-(X4-Pad9)") (class "Default")
      (node (ref "X4") (pin "9") (pinfunction "9_9") (pintype "passive"))
    )
    (net (code "88") (name "unconnected-(X4-Pad10)") (class "Default")
      (node (ref "X4") (pin "10") (pinfunction "10_10") (pintype "passive"))
    )
  )
)
